# InterfaceBoard_1.net
KiCad netlist of a schematic drawn in Altium Designer
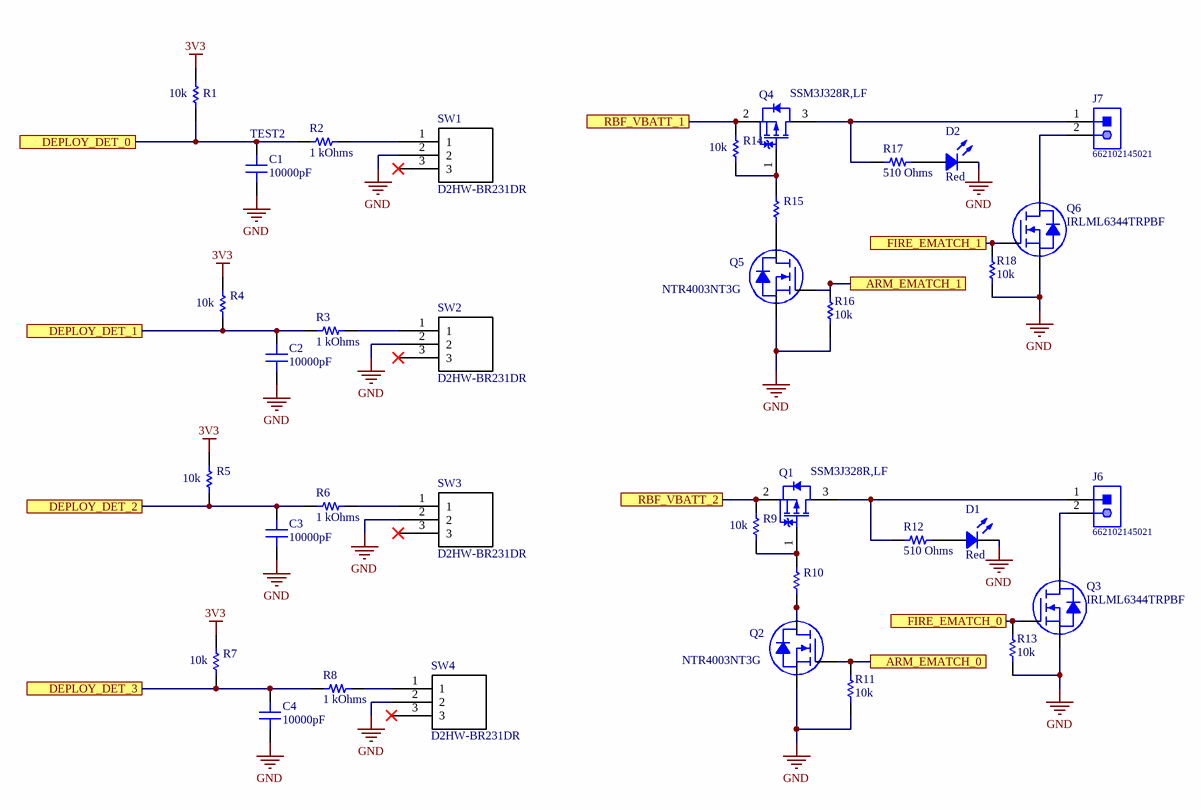
[diagram p0: InterfaceBoard_1.SchDoc]

(export (version "E")
  (design (tool "Eeschema 10.0.6"))
  (components
    (comp (ref "C1")
      (value "10000pF")
      (footprint "CAP 0603_1608")
      (description "CAP CER 10000PF 16V X7R 0603")
      (fields (field (name "PART NUMBER") "C0603S103K4RACTU") (field (name "MANUFACTURER") "KEMET"))
      (libsource (lib "Celestial Altium Library - altium_library") (part "Capacitor"))
    )
    (comp (ref "C2")
      (value "10000pF")
      (footprint "CAP 0603_1608")
      (description "CAP CER 10000PF 16V X7R 0603")
      (fields (field (name "PART NUMBER") "C0603S103K4RACTU") (field (name "MANUFACTURER") "KEMET"))
      (libsource (lib "Celestial Altium Library - altium_library") (part "Capacitor"))
    )
    (comp (ref "C3")
      (value "10000pF")
      (footprint "CAP 0603_1608")
      (description "CAP CER 10000PF 16V X7R 0603")
      (fields (field (name "PART NUMBER") "C0603S103K4RACTU") (field (name "MANUFACTURER") "KEMET"))
      (libsource (lib "Celestial Altium Library - altium_library") (part "Capacitor"))
    )
    (comp (ref "C4")
      (value "10000pF")
      (footprint "CAP 0603_1608")
      (description "CAP CER 10000PF 16V X7R 0603")
      (fields (field (name "PART NUMBER") "C0603S103K4RACTU") (field (name "MANUFACTURER") "KEMET"))
      (libsource (lib "Celestial Altium Library - altium_library") (part "Capacitor"))
    )
    (comp (ref "D1")
      (value "Red")
      (footprint "LED 1206_3216 RED")
      (description "LED RED CHIP SMD")
      (fields (field (name "PART NUMBER") "HSMC-C350") (field (name "MANUFACTURER") "Broadcom Limited"))
      (libsource (lib "Celestial Altium Library - altium_library") (part "LED"))
    )
    (comp (ref "D2")
      (value "Red")
      (footprint "LED 1206_3216 RED")
      (description "LED RED CHIP SMD")
      (fields (field (name "PART NUMBER") "HSMC-C350") (field (name "MANUFACTURER") "Broadcom Limited"))
      (libsource (lib "Celestial Altium Library - altium_library") (part "LED"))
    )
    (comp (ref "J6")
      (value "662102145021")
      (footprint "662102145021")
      (description "SMT Male Header WR-MPC3, with SMT Solder Tabs, Right Angled, Single Row, pitch 3 mm, 2 pins")
      (fields (field (name "MANUFACTURER") "Wurth Elektronik") (field (name "PUBLISHER") "WurthElektronik"))
      (libsource (lib "Altium Content Vault") (part "WE-CN-1P-M-R2"))
    )
    (comp (ref "J7")
      (value "662102145021")
      (footprint "662102145021")
      (description "SMT Male Header WR-MPC3, with SMT Solder Tabs, Right Angled, Single Row, pitch 3 mm, 2 pins")
      (fields (field (name "MANUFACTURER") "Wurth Elektronik") (field (name "PUBLISHER") "WurthElektronik"))
      (libsource (lib "Altium Content Vault") (part "WE-CN-1P-M-R2"))
    )
    (comp (ref "Q1")
      (value "SSM3J328R,LF")
      (footprint "TOSH-SOT-23F_V")
      (fields (field (name "MANUFACTURER") "Toshiba"))
      (libsource (lib "Altium Content Vault") (part "PEMOS-GSD-3_C"))
    )
    (comp (ref "Q2")
      (value "NTR4003NT3G")
      (footprint "ON SEMI SOT-23-3")
      (description "MOSFET N-CH 30V 500MA SOT-23")
      (fields (field (name "MANUFACTURER") "ON Semiconductor"))
      (libsource (lib "Celestial Altium Library - altium_library") (part "ON SEMI MOSFET N-CH SOT-23-3"))
    )
    (comp (ref "Q3")
      (value "IRLML6344TRPBF")
      (footprint "INFINEON SOT-23-3")
      (description "MOSFET N-CH 30V 5A SOT23")
      (fields (field (name "MANUFACTURER") "Infineon Technologies"))
      (libsource (lib "Celestial Altium Library - altium_library") (part "INFINEON MOSFET N-CH SOT-23-3 GSD"))
    )
    (comp (ref "Q4")
      (value "SSM3J328R,LF")
      (footprint "TOSH-SOT-23F_V")
      (fields (field (name "MANUFACTURER") "Toshiba"))
      (libsource (lib "Altium Content Vault") (part "PEMOS-GSD-3_C"))
    )
    (comp (ref "Q5")
      (value "NTR4003NT3G")
      (footprint "ON SEMI SOT-23-3")
      (description "MOSFET N-CH 30V 500MA SOT-23")
      (fields (field (name "MANUFACTURER") "ON Semiconductor"))
      (libsource (lib "Celestial Altium Library - altium_library") (part "ON SEMI MOSFET N-CH SOT-23-3"))
    )
    (comp (ref "Q6")
      (value "IRLML6344TRPBF")
      (footprint "INFINEON SOT-23-3")
      (description "MOSFET N-CH 30V 5A SOT23")
      (fields (field (name "MANUFACTURER") "Infineon Technologies"))
      (libsource (lib "Celestial Altium Library - altium_library") (part "INFINEON MOSFET N-CH SOT-23-3 GSD"))
    )
    (comp (ref "R1")
      (value "10k")
      (footprint "RES 0603_1608")
      (description "Chip Resistor, 10 KOhm, +/- 1%, 100 mW, -55 to 155 degC, 0603 (1608 Metric), RoHS, Tape and Reel")
      (fields (field (name "MANUFACTURER") "Vishay Semiconductor") (field (name "Comment") "1 kOhms"))
      (libsource (lib "") (part "RES-2_1"))
    )
    (comp (ref "R2")
      (value "1 kOhms")
      (footprint "RES 0603_1608")
      (description "RES SMD 1K OHM 0.1% 1/16W 0603")
      (fields
        (field (name "PART NUMBER") "CPF0603B1K0E")
        (field (name "MANUFACTURER") "TE Connectivity Passive Product")
      )
      (libsource (lib "Celestial Altium Library - altium_library") (part "Resistor"))
    )
    (comp (ref "R3")
      (value "1 kOhms")
      (footprint "RES 0603_1608")
      (description "RES SMD 1K OHM 0.1% 1/16W 0603")
      (fields
        (field (name "PART NUMBER") "CPF0603B1K0E")
        (field (name "MANUFACTURER") "TE Connectivity Passive Product")
      )
      (libsource (lib "Celestial Altium Library - altium_library") (part "Resistor"))
    )
    (comp (ref "R4")
      (value "10k")
      (footprint "RESC1609X50X30NL8T20")
      (description "Chip Resistor, 10 KOhm, +/- 1%, 100 mW, -55 to 155 degC, 0603 (1608 Metric), RoHS, Tape and Reel")
      (fields
        (field (name "MANUFACTURER") "Vishay Semiconductor")
        (field (name "Comment") "CRCW060310K0FKEA")
      )
      (libsource (lib "Altium Content Vault") (part "RES-2"))
    )
    (comp (ref "R5")
      (value "10k")
      (footprint "RES 0603_1608")
      (description "Chip Resistor, 10 KOhm, +/- 1%, 100 mW, -55 to 155 degC, 0603 (1608 Metric), RoHS, Tape and Reel")
      (fields (field (name "MANUFACTURER") "Vishay Semiconductor") (field (name "Comment") "1 kOhms"))
      (libsource (lib "") (part "RES-2_1"))
    )
    (comp (ref "R6")
      (value "1 kOhms")
      (footprint "RESC1609X50X30NL8T20")
      (description "RES SMD 1K OHM 0.1% 1/16W 0603")
      (fields
        (field (name "PART NUMBER") "CPF0603B1K0E")
        (field (name "MANUFACTURER") "TE Connectivity Passive Product")
      )
      (libsource (lib "Celestial Altium Library - altium_library") (part "Resistor"))
    )
    (comp (ref "R7")
      (value "10k")
      (footprint "RES 0603_1608")
      (description "Chip Resistor, 10 KOhm, +/- 1%, 100 mW, -55 to 155 degC, 0603 (1608 Metric), RoHS, Tape and Reel")
      (fields (field (name "MANUFACTURER") "Vishay Semiconductor") (field (name "Comment") "1 kOhms"))
      (libsource (lib "") (part "RES-2_1"))
    )
    (comp (ref "R8")
      (value "1 kOhms")
      (footprint "RESC1609X50X30NL8T20")
      (description "RES SMD 1K OHM 0.1% 1/16W 0603")
      (fields
        (field (name "PART NUMBER") "CPF0603B1K0E")
        (field (name "MANUFACTURER") "TE Connectivity Passive Product")
      )
      (libsource (lib "Celestial Altium Library - altium_library") (part "Resistor"))
    )
    (comp (ref "R9")
      (value "10k")
      (footprint "RESC1609X50X30NL8T20")
      (description "Chip Resistor, 10 KOhm, +/- 1%, 100 mW, -55 to 155 degC, 0603 (1608 Metric), RoHS, Tape and Reel")
      (fields
        (field (name "MANUFACTURER") "Vishay Semiconductor")
        (field (name "Comment") "CRCW060310K0FKEA")
      )
      (libsource (lib "Altium Content Vault") (part "RES-2"))
    )
    (comp (ref "R10")
      (value "CRCW060312K0FKEA")
      (footprint "RESC1609X50X30LL10T20")
      (fields (field (name "MANUFACTURER") "Vishay Dale"))
      (libsource (lib "Altium Content Vault") (part "RES"))
    )
    (comp (ref "R11")
      (value "10k")
      (footprint "RESC1609X50X30NL8T20")
      (description "Chip Resistor, 10 KOhm, +/- 1%, 100 mW, -55 to 155 degC, 0603 (1608 Metric), RoHS, Tape and Reel")
      (fields
        (field (name "MANUFACTURER") "Vishay Semiconductor")
        (field (name "Comment") "CRCW060310K0FKEA")
      )
      (libsource (lib "Altium Content Vault") (part "RES-2"))
    )
    (comp (ref "R12")
      (value "510 Ohms")
      (footprint "RES 0603_1608")
      (description "RES SMD 510 OHM 1% 1/4W 0603")
      (fields (field (name "PART NUMBER") "CRCW0603510RFKEAHP") (field (name "MANUFACTURER") "Vishay Dale"))
      (libsource (lib "Celestial Altium Library - altium_library") (part "Resistor"))
    )
    (comp (ref "R13")
      (value "10k")
      (footprint "RESC1609X50X30NL8T20")
      (description "Chip Resistor, 10 KOhm, +/- 1%, 100 mW, -55 to 155 degC, 0603 (1608 Metric), RoHS, Tape and Reel")
      (fields
        (field (name "MANUFACTURER") "Vishay Semiconductor")
        (field (name "Comment") "CRCW060310K0FKEA")
      )
      (libsource (lib "Altium Content Vault") (part "RES-2"))
    )
    (comp (ref "R14")
      (value "10k")
      (footprint "RESC1609X50X30NL8T20")
      (description "Chip Resistor, 10 KOhm, +/- 1%, 100 mW, -55 to 155 degC, 0603 (1608 Metric), RoHS, Tape and Reel")
      (fields
        (field (name "MANUFACTURER") "Vishay Semiconductor")
        (field (name "Comment") "CRCW060310K0FKEA")
      )
      (libsource (lib "Altium Content Vault") (part "RES-2"))
    )
    (comp (ref "R15")
      (value "CRCW060312K0FKEA")
      (footprint "RESC1609X50X30LL10T20")
      (fields (field (name "MANUFACTURER") "Vishay Dale"))
      (libsource (lib "Altium Content Vault") (part "RES"))
    )
    (comp (ref "R16")
      (value "10k")
      (footprint "RESC1609X50X30NL8T20")
      (description "Chip Resistor, 10 KOhm, +/- 1%, 100 mW, -55 to 155 degC, 0603 (1608 Metric), RoHS, Tape and Reel")
      (fields
        (field (name "MANUFACTURER") "Vishay Semiconductor")
        (field (name "Comment") "CRCW060310K0FKEA")
      )
      (libsource (lib "Altium Content Vault") (part "RES-2"))
    )
    (comp (ref "R17")
      (value "510 Ohms")
      (footprint "RES 0603_1608")
      (description "RES SMD 510 OHM 1% 1/4W 0603")
      (fields (field (name "PART NUMBER") "CRCW0603510RFKEAHP") (field (name "MANUFACTURER") "Vishay Dale"))
      (libsource (lib "Celestial Altium Library - altium_library") (part "Resistor"))
    )
    (comp (ref "R18")
      (value "10k")
      (footprint "RESC1609X50X30NL8T20")
      (description "Chip Resistor, 10 KOhm, +/- 1%, 100 mW, -55 to 155 degC, 0603 (1608 Metric), RoHS, Tape and Reel")
      (fields
        (field (name "MANUFACTURER") "Vishay Semiconductor")
        (field (name "Comment") "CRCW060310K0FKEA")
      )
      (libsource (lib "Altium Content Vault") (part "RES-2"))
    )
    (comp (ref "SW1") (value "D2HW-BR231DR") (libsource (lib "D2HW-BR231") (part "D2HW-BR231DR")))
    (comp (ref "SW2") (value "D2HW-BR231DR") (libsource (lib "D2HW-BR231") (part "D2HW-BR231DR")))
    (comp (ref "SW3") (value "D2HW-BR231DR") (libsource (lib "D2HW-BR231") (part "D2HW-BR231DR")))
    (comp (ref "SW4") (value "D2HW-BR231DR") (libsource (lib "D2HW-BR231") (part "D2HW-BR231DR")))
  )
  (nets
    (net (code "1") (name "/ARM_EMATCH_0") (class "Default")
      (node (ref "Q2") (pin "1") (pinfunction "G_1") (pintype "passive"))
      (node (ref "R11") (pin "1") (pinfunction "1_1") (pintype "passive"))
    )
    (net (code "2") (name "/ARM_EMATCH_1") (class "Default")
      (node (ref "Q5") (pin "1") (pinfunction "G_1") (pintype "passive"))
      (node (ref "R16") (pin "1") (pinfunction "1_1") (pintype "passive"))
    )
    (net (code "3") (name "/DEPLOY_DET_0") (class "Default")
      (node (ref "C1") (pin "2") (pinfunction "2_2") (pintype "passive"))
      (node (ref "R1") (pin "2") (pinfunction "2_2") (pintype "passive"))
      (node (ref "R2") (pin "1") (pinfunction "1_1") (pintype "passive"))
    )
    (net (code "4") (name "/DEPLOY_DET_1") (class "Default")
      (node (ref "C2") (pin "2") (pinfunction "2_2") (pintype "passive"))
      (node (ref "R3") (pin "1") (pinfunction "1_1") (pintype "passive"))
      (node (ref "R4") (pin "1") (pinfunction "1_1") (pintype "passive"))
    )
    (net (code "5") (name "/DEPLOY_DET_2") (class "Default")
      (node (ref "C3") (pin "2") (pinfunction "2_2") (pintype "passive"))
      (node (ref "R5") (pin "2") (pinfunction "2_2") (pintype "passive"))
      (node (ref "R6") (pin "1") (pinfunction "1_1") (pintype "passive"))
    )
    (net (code "6") (name "/DEPLOY_DET_3") (class "Default")
      (node (ref "C4") (pin "2") (pinfunction "2_2") (pintype "passive"))
      (node (ref "R7") (pin "2") (pinfunction "2_2") (pintype "passive"))
      (node (ref "R8") (pin "1") (pinfunction "1_1") (pintype "passive"))
    )
    (net (code "7") (name "/FIRE_EMATCH_0") (class "Default")
      (node (ref "Q3") (pin "1") (pinfunction "G_1") (pintype "passive"))
      (node (ref "R13") (pin "1") (pinfunction "1_1") (pintype "passive"))
    )
    (net (code "8") (name "/FIRE_EMATCH_1") (class "Default")
      (node (ref "Q6") (pin "1") (pinfunction "G_1") (pintype "passive"))
      (node (ref "R18") (pin "1") (pinfunction "1_1") (pintype "passive"))
    )
    (net (code "9") (name "/RBF_VBATT_1") (class "Default")
      (node (ref "Q4") (pin "2") (pinfunction "S_2") (pintype "passive"))
      (node (ref "R14") (pin "2") (pinfunction "2_2") (pintype "passive"))
    )
    (net (code "10") (name "/RBF_VBATT_2") (class "Default")
      (node (ref "Q1") (pin "2") (pinfunction "S_2") (pintype "passive"))
      (node (ref "R9") (pin "2") (pinfunction "2_2") (pintype "passive"))
    )
    (net (code "11") (name "3V3") (class "Default")
      (node (ref "R1") (pin "2") (pinfunction "2_2") (pintype "passive"))
      (node (ref "R4") (pin "2") (pinfunction "2_2") (pintype "passive"))
      (node (ref "R5") (pin "2") (pinfunction "2_2") (pintype "passive"))
      (node (ref "R7") (pin "2") (pinfunction "2_2") (pintype "passive"))
    )
    (net (code "12") (name "GND") (class "Default")
      (node (ref "C1") (pin "1") (pinfunction "1_1") (pintype "passive"))
      (node (ref "C2") (pin "1") (pinfunction "1_1") (pintype "passive"))
      (node (ref "C3") (pin "1") (pinfunction "1_1") (pintype "passive"))
      (node (ref "C4") (pin "1") (pinfunction "1_1") (pintype "passive"))
      (node (ref "D1") (pin "2") (pinfunction "2_2") (pintype "passive"))
      (node (ref "D2") (pin "2") (pinfunction "2_2") (pintype "passive"))
      (node (ref "Q2") (pin "2") (pinfunction "S_2") (pintype "passive"))
      (node (ref "Q3") (pin "2") (pinfunction "S_2") (pintype "passive"))
      (node (ref "Q5") (pin "2") (pinfunction "S_2") (pintype "passive"))
      (node (ref "Q6") (pin "2") (pinfunction "S_2") (pintype "passive"))
      (node (ref "R11") (pin "2") (pinfunction "2_2") (pintype "passive"))
      (node (ref "R13") (pin "2") (pinfunction "2_2") (pintype "passive"))
      (node (ref "R16") (pin "2") (pinfunction "2_2") (pintype "passive"))
      (node (ref "R18") (pin "2") (pinfunction "2_2") (pintype "passive"))
      (node (ref "SW1") (pin "2") (pinfunction "2_2") (pintype "passive"))
      (node (ref "SW2") (pin "2") (pinfunction "2_2") (pintype "passive"))
      (node (ref "SW3") (pin "2") (pinfunction "2_2") (pintype "passive"))
      (node (ref "SW4") (pin "2") (pinfunction "2_2") (pintype "passive"))
    )
    (net (code "13") (name "Net-(D1-Pad1)") (class "Default")
      (node (ref "D1") (pin "1") (pinfunction "1_1") (pintype "passive"))
      (node (ref "R12") (pin "2") (pinfunction "2_2") (pintype "passive"))
    )
    (net (code "14") (name "Net-(D2-Pad1)") (class "Default")
      (node (ref "D2") (pin "1") (pinfunction "1_1") (pintype "passive"))
      (node (ref "R17") (pin "2") (pinfunction "2_2") (pintype "passive"))
    )
    (net (code "15") (name "Net-(Q1-D)") (class "Default")
      (node (ref "J6") (pin "1") (pinfunction "1_1") (pintype "passive"))
      (node (ref "Q1") (pin "3") (pinfunction "D_3") (pintype "passive"))
      (node (ref "R12") (pin "1") (pinfunction "1_1") (pintype "passive"))
    )
    (net (code "16") (name "Net-(Q1-G)") (class "Default")
      (node (ref "Q1") (pin "1") (pinfunction "G_1") (pintype "passive"))
      (node (ref "R10") (pin "2") (pinfunction "2_2") (pintype "passive"))
      (node (ref "R9") (pin "1") (pinfunction "1_1") (pintype "passive"))
    )
    (net (code "17") (name "Net-(Q2-D)") (class "Default")
      (node (ref "Q2") (pin "3") (pinfunction "D_3") (pintype "passive"))
      (node (ref "R10") (pin "1") (pinfunction "1_1") (pintype "passive"))
    )
    (net (code "18") (name "Net-(Q3-D)") (class "Default")
      (node (ref "J6") (pin "2") (pinfunction "2_2") (pintype "passive"))
      (node (ref "Q3") (pin "3") (pinfunction "D_3") (pintype "passive"))
    )
    (net (code "19") (name "Net-(Q4-D)") (class "Default")
      (node (ref "J7") (pin "1") (pinfunction "1_1") (pintype "passive"))
      (node (ref "Q4") (pin "3") (pinfunction "D_3") (pintype "passive"))
      (node (ref "R17") (pin "1") (pinfunction "1_1") (pintype "passive"))
    )
    (net (code "20") (name "Net-(Q4-G)") (class "Default")
      (node (ref "Q4") (pin "1") (pinfunction "G_1") (pintype "passive"))
      (node (ref "R14") (pin "1") (pinfunction "1_1") (pintype "passive"))
      (node (ref "R15") (pin "2") (pinfunction "2_2") (pintype "passive"))
    )
    (net (code "21") (name "Net-(Q5-D)") (class "Default")
      (node (ref "Q5") (pin "3") (pinfunction "D_3") (pintype "passive"))
      (node (ref "R15") (pin "1") (pinfunction "1_1") (pintype "passive"))
    )
    (net (code "22") (name "Net-(Q6-D)") (class "Default")
      (node (ref "J7") (pin "2") (pinfunction "2_2") (pintype "passive"))
      (node (ref "Q6") (pin "3") (pinfunction "D_3") (pintype "passive"))
    )
    (net (code "23") (name "Net-(R2-Pad2)") (class "Default")
      (node (ref "R2") (pin "2") (pinfunction "2_2") (pintype "passive"))
      (node (ref "SW1") (pin "1") (pinfunction "1_1") (pintype "passive"))
    )
    (net (code "24") (name "Net-(R3-Pad2)") (class "Default")
      (node (ref "R3") (pin "2") (pinfunction "2_2") (pintype "passive"))
      (node (ref "SW2") (pin "1") (pinfunction "1_1") (pintype "passive"))
    )
    (net (code "25") (name "Net-(R6-Pad2)") (class "Default")
      (node (ref "R6") (pin "2") (pinfunction "2_2") (pintype "passive"))
      (node (ref "SW3") (pin "1") (pinfunction "1_1") (pintype "passive"))
    )
    (net (code "26") (name "Net-(R8-Pad2)") (class "Default")
      (node (ref "R8") (pin "2") (pinfunction "2_2") (pintype "passive"))
      (node (ref "SW4") (pin "1") (pinfunction "1_1") (pintype "passive"))
    )
    (net (code "27") (name "unconnected-(SW1-Pad3)") (class "Default")
      (node (ref "SW1") (pin "3") (pinfunction "3_3") (pintype "passive+no_connect"))
    )
    (net (code "28") (name "unconnected-(SW2-Pad3)") (class "Default")
      (node (ref "SW2") (pin "3") (pinfunction "3_3") (pintype "passive+no_connect"))
    )
    (net (code "29") (name "unconnected-(SW3-Pad3)") (class "Default")
      (node (ref "SW3") (pin "3") (pinfunction "3_3") (pintype "passive+no_connect"))
    )
    (net (code "30") (name "unconnected-(SW4-Pad3)") (class "Default")
      (node (ref "SW4") (pin "3") (pinfunction "3_3") (pintype "passive+no_connect"))
    )
  )
)
